# SHABlindRfShield.net
KiCad netlist of a schematic drawn in EAGLE
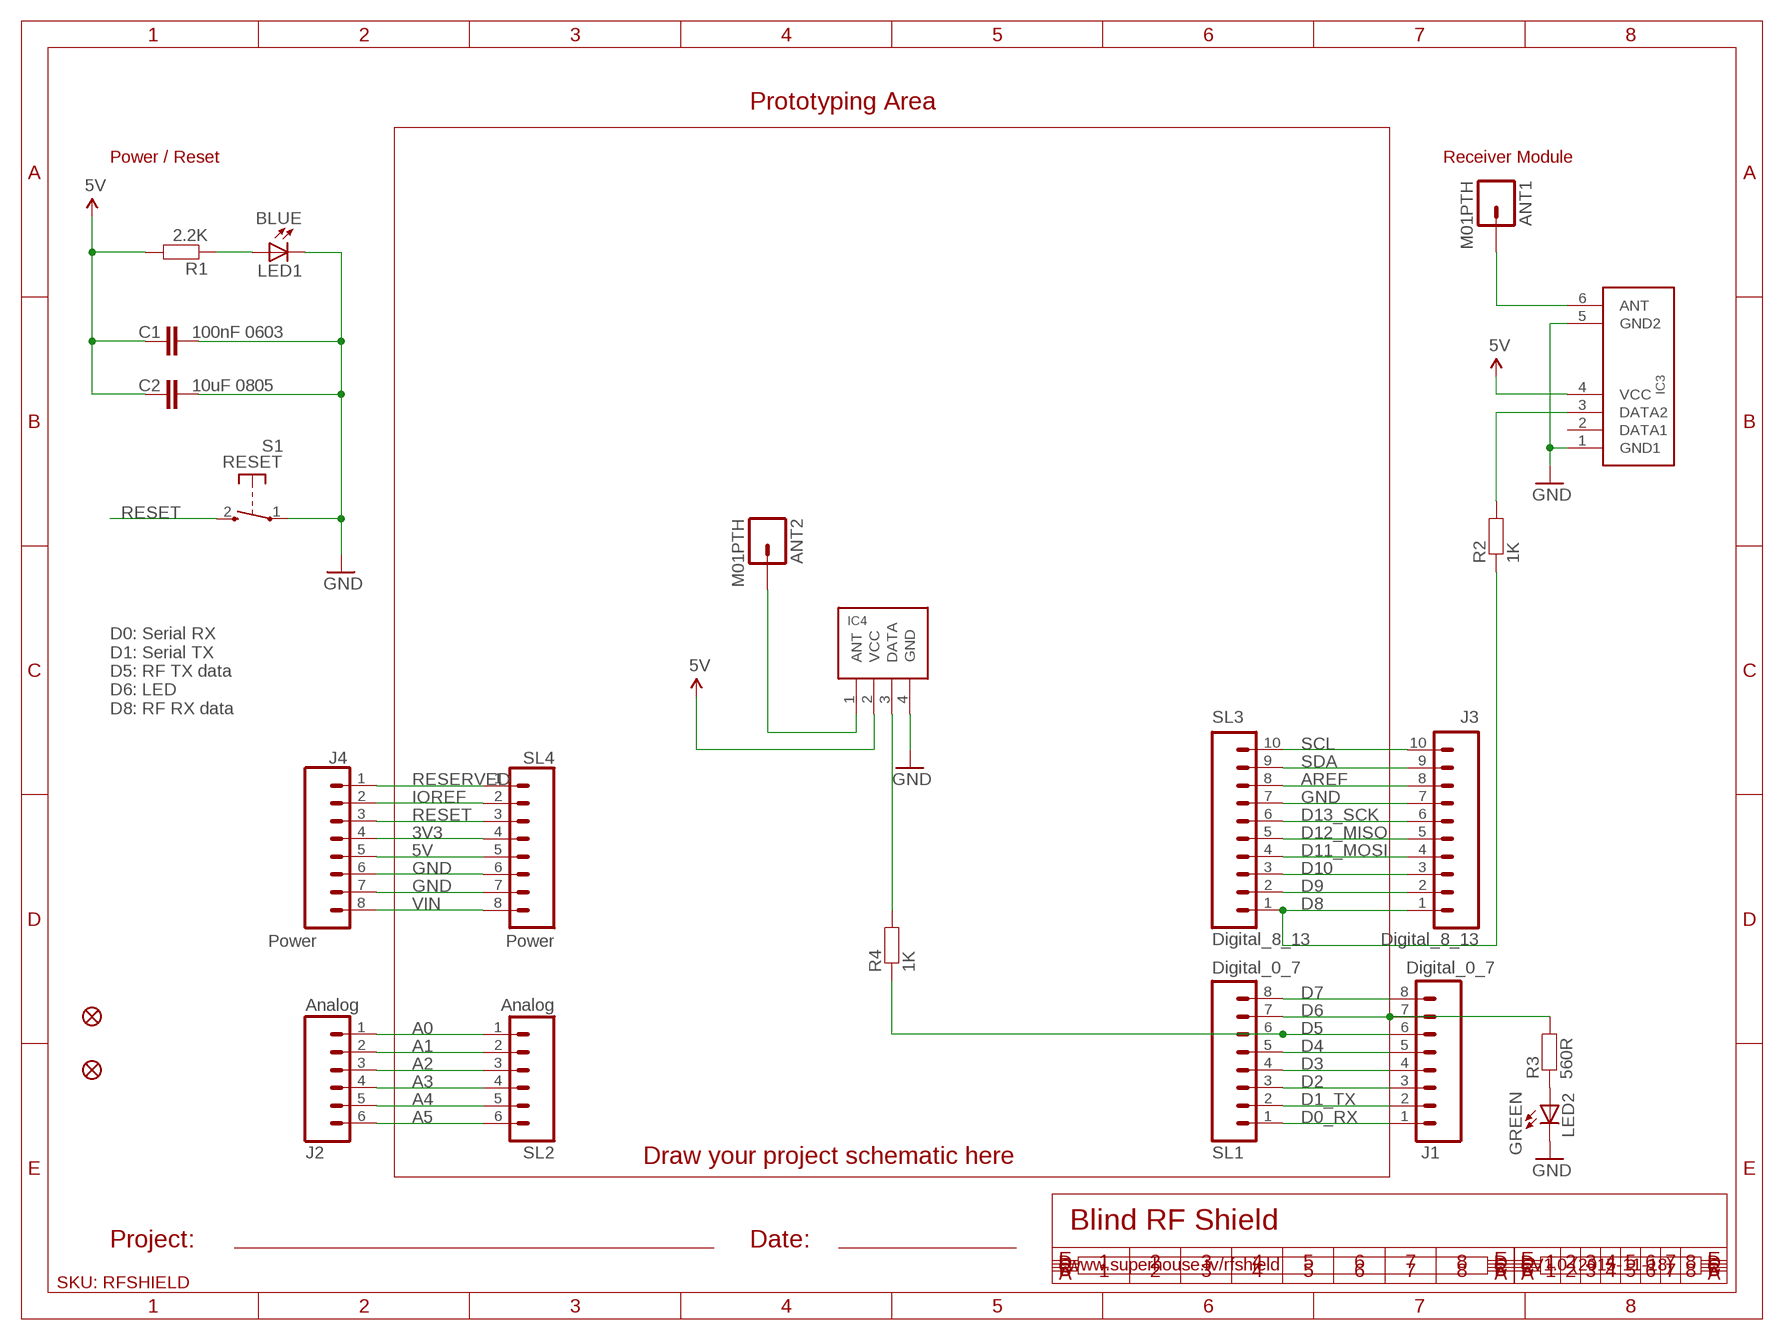
[diagram p0: schematic, sheet 1]

(export (version "E")
  (design (tool "Eeschema 10.0.6"))
  (components
    (comp (ref "ANT1")
      (value "M01PTH")
      (footprint "eagle-import:1X01")
      (libsource (lib "eagle-import") (part "M01PTH"))
    )
    (comp (ref "ANT2")
      (value "M01PTH")
      (footprint "eagle-import:1X01")
      (libsource (lib "eagle-import") (part "M01PTH"))
    )
    (comp (ref "C1")
      (value "100nF 0603")
      (footprint "eagle-import:0603")
      (libsource (lib "eagle-import") (part "CAP0603"))
    )
    (comp (ref "C2")
      (value "10uF 0805")
      (footprint "eagle-import:C0805")
      (libsource (lib "eagle-import") (part "C-EUC0805"))
    )
    (comp (ref "IC3")
      (value "RXB1")
      (footprint "eagle-import:RX-B1-SHORT-FLAT")
      (libsource (lib "eagle-import") (part "RXB1SHORTFLAT"))
    )
    (comp (ref "IC4")
      (value "TX-C1FLAT")
      (footprint "eagle-import:TX-C1-FLAT")
      (libsource (lib "eagle-import") (part "TX-C1FLAT"))
    )
    (comp (ref "J1")
      (value "Digital_0_7")
      (footprint "eagle-import:1X08")
      (libsource (lib "eagle-import") (part "M08"))
    )
    (comp (ref "J2")
      (value "Analog")
      (footprint "eagle-import:1X06")
      (libsource (lib "eagle-import") (part "M06SIP"))
    )
    (comp (ref "J3")
      (value "Digital_8_13")
      (footprint "eagle-import:1X10")
      (libsource (lib "eagle-import") (part "M100.1"))
    )
    (comp (ref "J4")
      (value "Power")
      (footprint "eagle-import:1X08")
      (libsource (lib "eagle-import") (part "M08"))
    )
    (comp (ref "LED1")
      (value "BLUE")
      (footprint "eagle-import:LED-0603")
      (libsource (lib "eagle-import") (part "LED0603"))
    )
    (comp (ref "LED2")
      (value "GREEN")
      (footprint "eagle-import:LED-0603")
      (libsource (lib "eagle-import") (part "LED0603"))
    )
    (comp (ref "R1")
      (value "2.2K")
      (footprint "eagle-import:0603")
      (libsource (lib "eagle-import") (part "RESISTOR0603"))
    )
    (comp (ref "R2")
      (value "1K")
      (footprint "eagle-import:0603")
      (libsource (lib "eagle-import") (part "RESISTOR0603"))
    )
    (comp (ref "R3")
      (value "560R")
      (footprint "eagle-import:0603")
      (libsource (lib "eagle-import") (part "RESISTOR0603"))
    )
    (comp (ref "R4")
      (value "1K")
      (footprint "eagle-import:0603")
      (libsource (lib "eagle-import") (part "RESISTOR0603"))
    )
    (comp (ref "S1")
      (value "RESET")
      (footprint "eagle-import:TACTILE_SWITCH_SMD_2PIN_TINY")
      (libsource (lib "eagle-import") (part "TAC_SWITCH_2PIN"))
    )
    (comp (ref "SL1")
      (value "Digital_0_7")
      (footprint "eagle-import:1X08")
      (libsource (lib "eagle-import") (part "M08"))
    )
    (comp (ref "SL2")
      (value "Analog")
      (footprint "eagle-import:1X06")
      (libsource (lib "eagle-import") (part "M06SIP"))
    )
    (comp (ref "SL3")
      (value "Digital_8_13")
      (footprint "eagle-import:1X10")
      (libsource (lib "eagle-import") (part "M100.1"))
    )
    (comp (ref "SL4")
      (value "Power")
      (footprint "eagle-import:1X08")
      (libsource (lib "eagle-import") (part "M08"))
    )
    (comp (ref "U$4")
      (value "FIDUCIAL1X2.5")
      (footprint "eagle-import:FIDUCIAL-1X2.5")
      (libsource (lib "eagle-import") (part "FIDUCIAL1X2.5"))
    )
    (comp (ref "U$5")
      (value "FIDUCIAL1X2.5")
      (footprint "eagle-import:FIDUCIAL-1X2.5")
      (libsource (lib "eagle-import") (part "FIDUCIAL1X2.5"))
    )
  )
  (nets
    (net (code "1") (name "/3V3") (class "Default")
      (node (ref "J4") (pin "4") (pinfunction "4_4") (pintype "passive"))
      (node (ref "SL4") (pin "4") (pinfunction "4_4") (pintype "passive"))
    )
    (net (code "2") (name "/A0") (class "Default")
      (node (ref "J2") (pin "1") (pinfunction "1_1") (pintype "passive"))
      (node (ref "SL2") (pin "1") (pinfunction "1_1") (pintype "passive"))
    )
    (net (code "3") (name "/A1") (class "Default")
      (node (ref "J2") (pin "2") (pinfunction "2_2") (pintype "passive"))
      (node (ref "SL2") (pin "2") (pinfunction "2_2") (pintype "passive"))
    )
    (net (code "4") (name "/A2") (class "Default")
      (node (ref "J2") (pin "3") (pinfunction "3_3") (pintype "passive"))
      (node (ref "SL2") (pin "3") (pinfunction "3_3") (pintype "passive"))
    )
    (net (code "5") (name "/A3") (class "Default")
      (node (ref "J2") (pin "4") (pinfunction "4_4") (pintype "passive"))
      (node (ref "SL2") (pin "4") (pinfunction "4_4") (pintype "passive"))
    )
    (net (code "6") (name "/A4") (class "Default")
      (node (ref "J2") (pin "5") (pinfunction "5_5") (pintype "passive"))
      (node (ref "SL2") (pin "5") (pinfunction "5_5") (pintype "passive"))
    )
    (net (code "7") (name "/A5") (class "Default")
      (node (ref "J2") (pin "6") (pinfunction "6_6") (pintype "passive"))
      (node (ref "SL2") (pin "6") (pinfunction "6_6") (pintype "passive"))
    )
    (net (code "8") (name "/AREF") (class "Default")
      (node (ref "J3") (pin "8") (pinfunction "8_8") (pintype "passive"))
      (node (ref "SL3") (pin "8") (pinfunction "8_8") (pintype "passive"))
    )
    (net (code "9") (name "/D0_RX") (class "Default")
      (node (ref "J1") (pin "1") (pinfunction "1_1") (pintype "passive"))
      (node (ref "SL1") (pin "1") (pinfunction "1_1") (pintype "passive"))
    )
    (net (code "10") (name "/D1_TX") (class "Default")
      (node (ref "J1") (pin "2") (pinfunction "2_2") (pintype "passive"))
      (node (ref "SL1") (pin "2") (pinfunction "2_2") (pintype "passive"))
    )
    (net (code "11") (name "/D2") (class "Default")
      (node (ref "J1") (pin "3") (pinfunction "3_3") (pintype "passive"))
      (node (ref "SL1") (pin "3") (pinfunction "3_3") (pintype "passive"))
    )
    (net (code "12") (name "/D3") (class "Default")
      (node (ref "J1") (pin "4") (pinfunction "4_4") (pintype "passive"))
      (node (ref "SL1") (pin "4") (pinfunction "4_4") (pintype "passive"))
    )
    (net (code "13") (name "/D4") (class "Default")
      (node (ref "J1") (pin "5") (pinfunction "5_5") (pintype "passive"))
      (node (ref "SL1") (pin "5") (pinfunction "5_5") (pintype "passive"))
    )
    (net (code "14") (name "/D5") (class "Default")
      (node (ref "J1") (pin "6") (pinfunction "6_6") (pintype "passive"))
      (node (ref "R4") (pin "1") (pinfunction "1_1") (pintype "passive"))
      (node (ref "SL1") (pin "6") (pinfunction "6_6") (pintype "passive"))
    )
    (net (code "15") (name "/D6") (class "Default")
      (node (ref "J1") (pin "7") (pinfunction "7_7") (pintype "passive"))
      (node (ref "R3") (pin "2") (pinfunction "2_2") (pintype "passive"))
      (node (ref "SL1") (pin "7") (pinfunction "7_7") (pintype "passive"))
    )
    (net (code "16") (name "/D7") (class "Default")
      (node (ref "J1") (pin "8") (pinfunction "8_8") (pintype "passive"))
      (node (ref "SL1") (pin "8") (pinfunction "8_8") (pintype "passive"))
    )
    (net (code "17") (name "/D8") (class "Default")
      (node (ref "J3") (pin "1") (pinfunction "1_1") (pintype "passive"))
      (node (ref "R2") (pin "1") (pinfunction "1_1") (pintype "passive"))
      (node (ref "SL3") (pin "1") (pinfunction "1_1") (pintype "passive"))
    )
    (net (code "18") (name "/D9") (class "Default")
      (node (ref "J3") (pin "2") (pinfunction "2_2") (pintype "passive"))
      (node (ref "SL3") (pin "2") (pinfunction "2_2") (pintype "passive"))
    )
    (net (code "19") (name "/D10") (class "Default")
      (node (ref "J3") (pin "3") (pinfunction "3_3") (pintype "passive"))
      (node (ref "SL3") (pin "3") (pinfunction "3_3") (pintype "passive"))
    )
    (net (code "20") (name "/D11_MOSI") (class "Default")
      (node (ref "J3") (pin "4") (pinfunction "4_4") (pintype "passive"))
      (node (ref "SL3") (pin "4") (pinfunction "4_4") (pintype "passive"))
    )
    (net (code "21") (name "/D12_MISO") (class "Default")
      (node (ref "J3") (pin "5") (pinfunction "5_5") (pintype "passive"))
      (node (ref "SL3") (pin "5") (pinfunction "5_5") (pintype "passive"))
    )
    (net (code "22") (name "/D13_SCK") (class "Default")
      (node (ref "J3") (pin "6") (pinfunction "6_6") (pintype "passive"))
      (node (ref "SL3") (pin "6") (pinfunction "6_6") (pintype "passive"))
    )
    (net (code "23") (name "/IOREF") (class "Default")
      (node (ref "J4") (pin "2") (pinfunction "2_2") (pintype "passive"))
      (node (ref "SL4") (pin "2") (pinfunction "2_2") (pintype "passive"))
    )
    (net (code "24") (name "/RESERVED") (class "Default")
      (node (ref "J4") (pin "1") (pinfunction "1_1") (pintype "passive"))
      (node (ref "SL4") (pin "1") (pinfunction "1_1") (pintype "passive"))
    )
    (net (code "25") (name "/RESET") (class "Default")
      (node (ref "J4") (pin "3") (pinfunction "3_3") (pintype "passive"))
      (node (ref "S1") (pin "2") (pinfunction "S_2") (pintype "passive"))
      (node (ref "SL4") (pin "3") (pinfunction "3_3") (pintype "passive"))
    )
    (net (code "26") (name "/SCL") (class "Default")
      (node (ref "J3") (pin "10") (pinfunction "10_10") (pintype "passive"))
      (node (ref "SL3") (pin "10") (pinfunction "10_10") (pintype "passive"))
    )
    (net (code "27") (name "/SDA") (class "Default")
      (node (ref "J3") (pin "9") (pinfunction "9_9") (pintype "passive"))
      (node (ref "SL3") (pin "9") (pinfunction "9_9") (pintype "passive"))
    )
    (net (code "28") (name "/VIN") (class "Default")
      (node (ref "J4") (pin "8") (pinfunction "8_8") (pintype "passive"))
      (node (ref "SL4") (pin "8") (pinfunction "8_8") (pintype "passive"))
    )
    (net (code "29") (name "5V") (class "Default")
      (node (ref "C1") (pin "1") (pinfunction "1_1") (pintype "passive"))
      (node (ref "C2") (pin "2") (pinfunction "2_2") (pintype "passive"))
      (node (ref "IC3") (pin "4") (pinfunction "VCC_4") (pintype "bidirectional"))
      (node (ref "IC4") (pin "2") (pinfunction "VCC_2") (pintype "power_in"))
      (node (ref "J4") (pin "5") (pinfunction "5_5") (pintype "passive"))
      (node (ref "R1") (pin "2") (pinfunction "2_2") (pintype "passive"))
      (node (ref "SL4") (pin "5") (pinfunction "5_5") (pintype "passive"))
    )
    (net (code "30") (name "GND") (class "Default")
      (node (ref "C1") (pin "2") (pinfunction "2_2") (pintype "passive"))
      (node (ref "C2") (pin "1") (pinfunction "1_1") (pintype "passive"))
      (node (ref "IC3") (pin "1") (pinfunction "GND1_1") (pintype "bidirectional"))
      (node (ref "IC3") (pin "5") (pinfunction "GND2_5") (pintype "bidirectional"))
      (node (ref "IC4") (pin "4") (pinfunction "GND_4") (pintype "power_in"))
      (node (ref "J3") (pin "7") (pinfunction "7_7") (pintype "passive"))
      (node (ref "J4") (pin "6") (pinfunction "6_6") (pintype "passive"))
      (node (ref "J4") (pin "7") (pinfunction "7_7") (pintype "passive"))
      (node (ref "LED1") (pin "C") (pinfunction "C_C") (pintype "passive"))
      (node (ref "LED2") (pin "C") (pinfunction "C_C") (pintype "passive"))
      (node (ref "S1") (pin "1") (pinfunction "P_1") (pintype "passive"))
      (node (ref "SL3") (pin "7") (pinfunction "7_7") (pintype "passive"))
      (node (ref "SL4") (pin "6") (pinfunction "6_6") (pintype "passive"))
      (node (ref "SL4") (pin "7") (pinfunction "7_7") (pintype "passive"))
    )
    (net (code "31") (name "Net-(IC3-ANT)") (class "Default")
      (node (ref "ANT1") (pin "1") (pinfunction "1_1") (pintype "passive"))
      (node (ref "IC3") (pin "6") (pinfunction "ANT_6") (pintype "bidirectional"))
    )
    (net (code "32") (name "Net-(IC3-DATA2)") (class "Default")
      (node (ref "IC3") (pin "3") (pinfunction "DATA2_3") (pintype "bidirectional"))
      (node (ref "R2") (pin "2") (pinfunction "2_2") (pintype "passive"))
    )
    (net (code "33") (name "Net-(IC4-ANT)") (class "Default")
      (node (ref "ANT2") (pin "1") (pinfunction "1_1") (pintype "passive"))
      (node (ref "IC4") (pin "1") (pinfunction "ANT_1") (pintype "output"))
    )
    (net (code "34") (name "Net-(IC4-DATA)") (class "Default")
      (node (ref "IC4") (pin "3") (pinfunction "DATA_3") (pintype "input"))
      (node (ref "R4") (pin "2") (pinfunction "2_2") (pintype "passive"))
    )
    (net (code "35") (name "Net-(LED1-PadA)") (class "Default")
      (node (ref "LED1") (pin "A") (pinfunction "A_A") (pintype "passive"))
      (node (ref "R1") (pin "1") (pinfunction "1_1") (pintype "passive"))
    )
    (net (code "36") (name "Net-(LED2-PadA)") (class "Default")
      (node (ref "LED2") (pin "A") (pinfunction "A_A") (pintype "passive"))
      (node (ref "R3") (pin "1") (pinfunction "1_1") (pintype "passive"))
    )
    (net (code "37") (name "unconnected-(IC3-DATA1-Pad2)") (class "Default")
      (node (ref "IC3") (pin "2") (pinfunction "DATA1_2") (pintype "bidirectional"))
    )
  )
)
